# Sheet3.net
KiCad netlist of a schematic drawn in Altium Designer
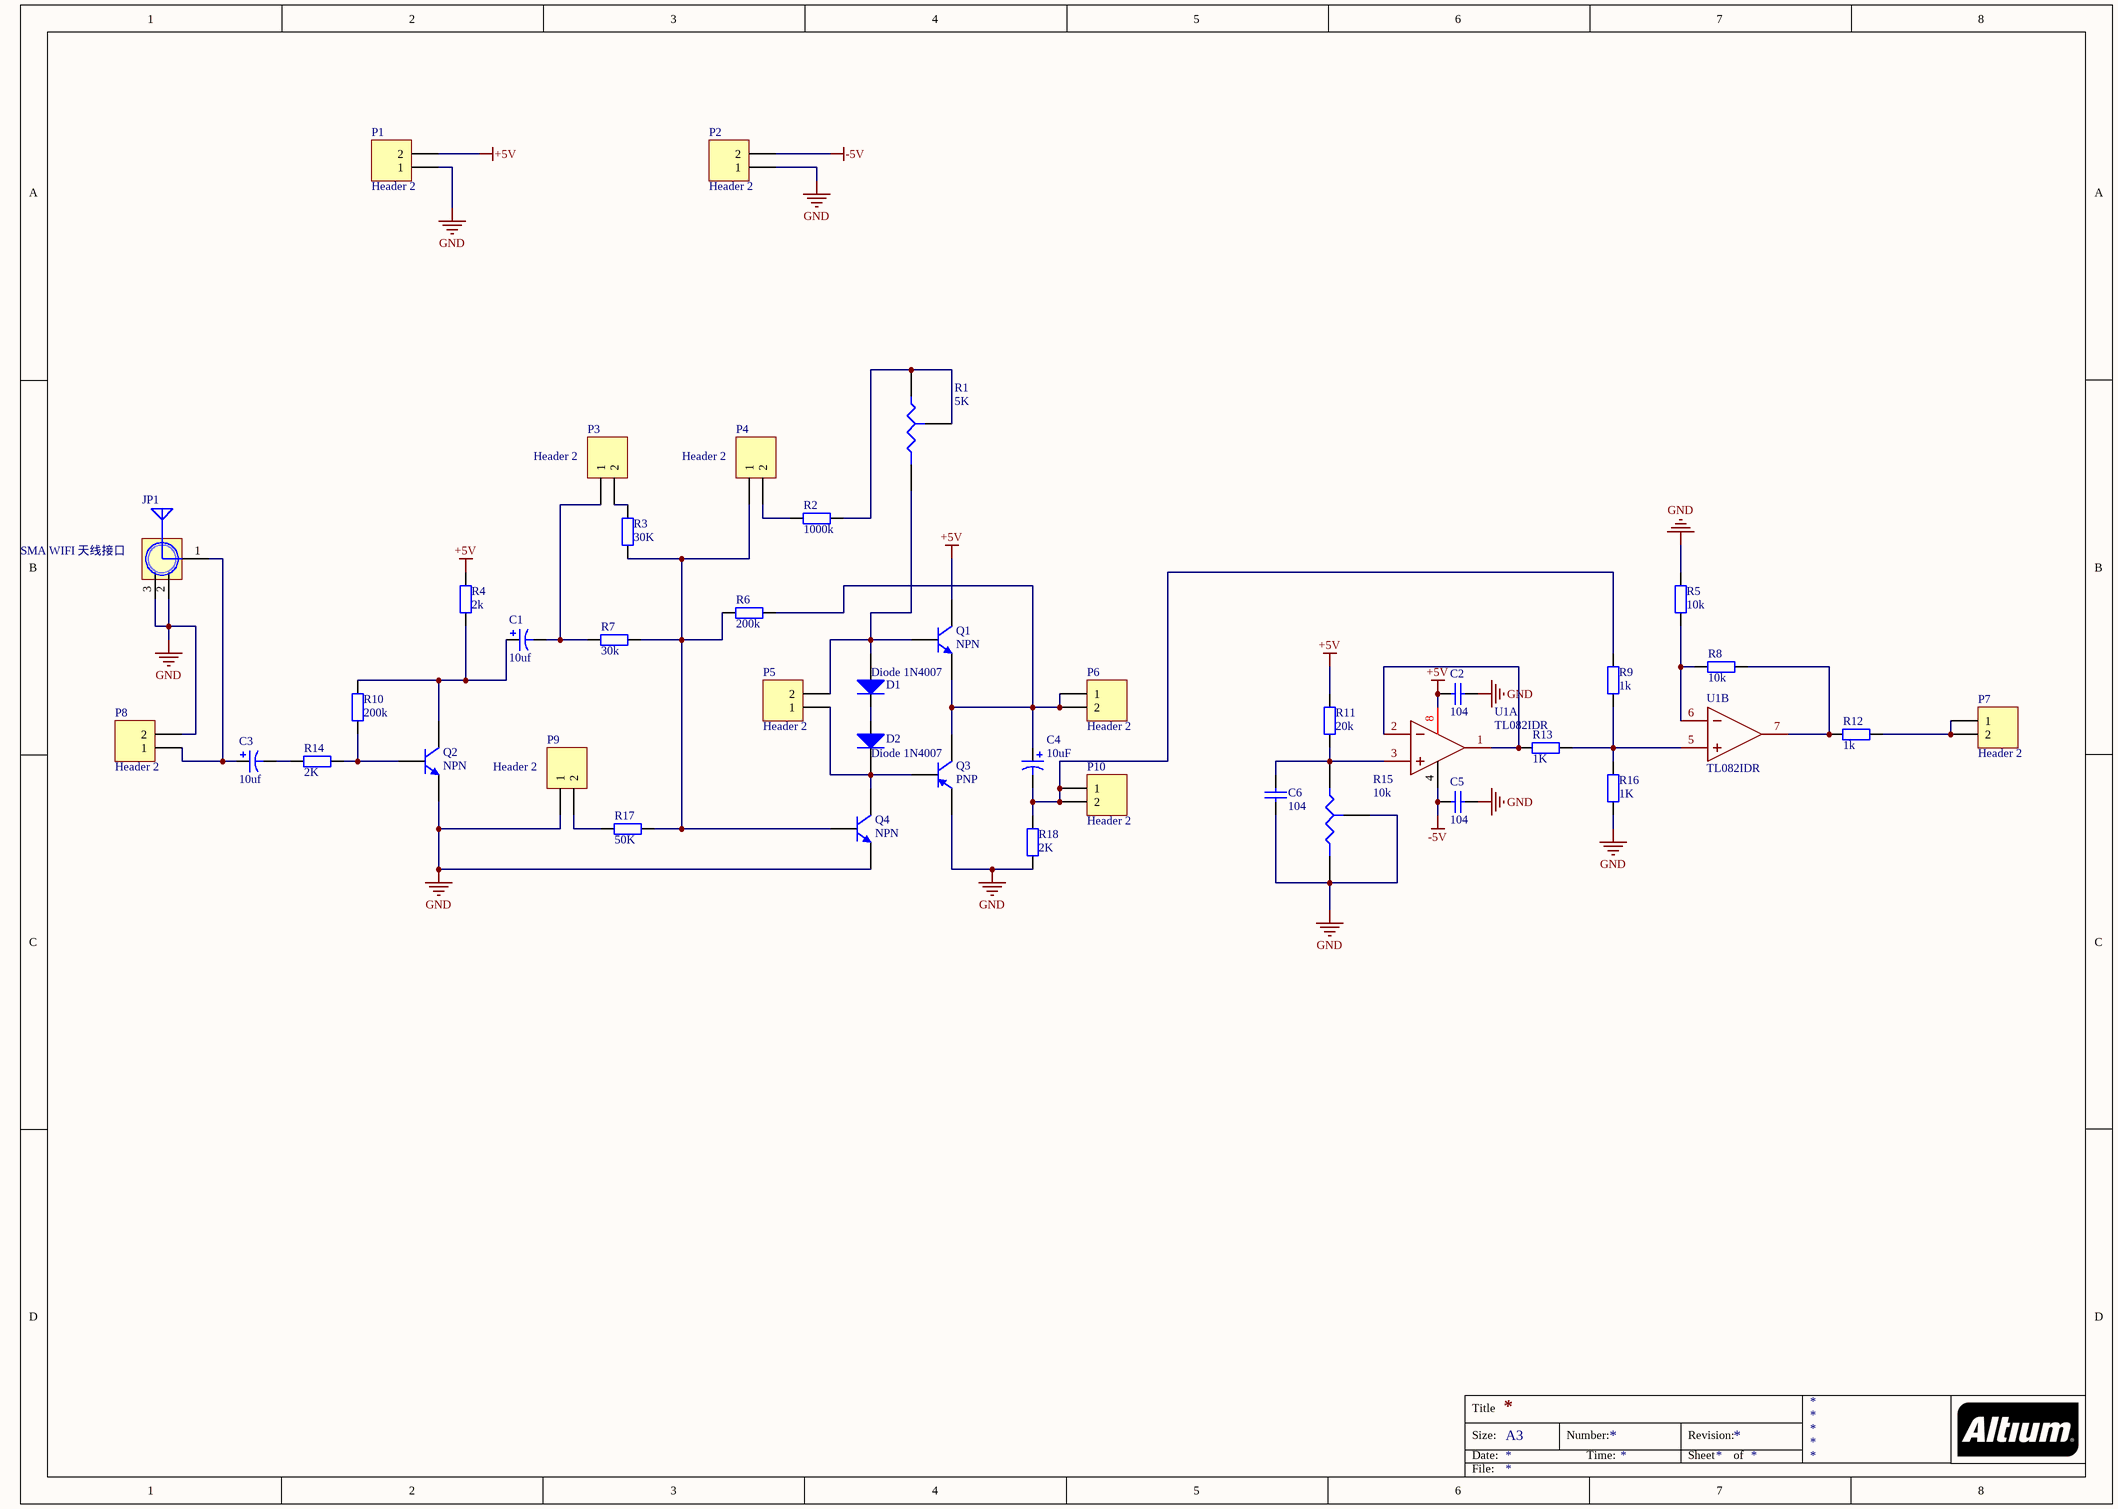
[diagram p0: Sheet3.SchDoc]

(export (version "E")
  (design (tool "Eeschema 10.0.6"))
  (components
    (comp (ref "C1")
      (value "10uf")
      (footprint "CAP 5.0*10*16 - BK")
      (description "Polarized Capacitor (Radial)")
      (fields (field (name "PUBLISHER") "Altium Limited"))
      (libsource (lib "Miscellaneous Devices") (part "Cap Pol1"))
    )
    (comp (ref "C2")
      (value "104")
      (footprint "CC 2.2*5")
      (description "Capacitor")
      (fields (field (name "PUBLISHER") "Altium Limited"))
      (libsource (lib "Miscellaneous Devices") (part "Cap"))
    )
    (comp (ref "C3")
      (value "10uf")
      (footprint "CAP 5.0*10*16 - BK")
      (description "Polarized Capacitor (Radial)")
      (fields (field (name "PUBLISHER") "Altium Limited"))
      (libsource (lib "Miscellaneous Devices") (part "Cap Pol1"))
    )
    (comp (ref "C4")
      (value "10uF")
      (footprint "CAP 5.0*10*16 - BK")
      (description "Polarized Capacitor (Radial)")
      (fields (field (name "PUBLISHER") "Altium Limited"))
      (libsource (lib "Miscellaneous Devices") (part "Cap Pol1"))
    )
    (comp (ref "C5")
      (value "104")
      (footprint "CC 2.2*5")
      (description "Capacitor")
      (fields (field (name "PUBLISHER") "Altium Limited"))
      (libsource (lib "Miscellaneous Devices") (part "Cap"))
    )
    (comp (ref "C6")
      (value "104")
      (footprint "CC 2.2*5")
      (description "Capacitor")
      (fields (field (name "PUBLISHER") "Altium Limited"))
      (libsource (lib "Miscellaneous Devices") (part "Cap"))
    )
    (comp (ref "D1")
      (value "Diode 1N4007")
      (footprint "DO-41")
      (description "1 Amp General Purpose Rectifier")
      (fields (field (name "PUBLISHER") "Altium Limited"))
      (libsource (lib "Miscellaneous Devices") (part "Diode 1N4007"))
    )
    (comp (ref "D2")
      (value "Diode 1N4007")
      (footprint "DO-41")
      (description "1 Amp General Purpose Rectifier")
      (fields (field (name "PUBLISHER") "Altium Limited"))
      (libsource (lib "Miscellaneous Devices") (part "Diode 1N4007"))
    )
    (comp (ref "JP1")
      (value "SMA WIFI 天线接口")
      (footprint "SMA-KE-LI")
      (description "SMA-2.4G射频天线接口")
      (fields (field (name "版权归属") "源创客"))
      (libsource (lib "14.1 - 天线") (part "SMA"))
    )
    (comp (ref "P1")
      (value "Header 2")
      (footprint "XH2.54-LI-2P")
      (description "Header, 2-Pin")
      (fields (field (name "PUBLISHER") "Altium Limited"))
      (libsource (lib "") (part "Header 2_1"))
    )
    (comp (ref "P2")
      (value "Header 2")
      (footprint "XH2.54-LI-2P")
      (description "Header, 2-Pin")
      (fields (field (name "PUBLISHER") "Altium Limited"))
      (libsource (lib "") (part "Header 2_1"))
    )
    (comp (ref "P3")
      (value "Header 2")
      (footprint "XH2.54-LI-2P")
      (description "Header, 2-Pin")
      (fields (field (name "PUBLISHER") "Altium Limited"))
      (libsource (lib "Miscellaneous Connectors") (part "Header 2"))
    )
    (comp (ref "P4")
      (value "Header 2")
      (footprint "XH2.54-LI-2P")
      (description "Header, 2-Pin")
      (fields (field (name "PUBLISHER") "Altium Limited"))
      (libsource (lib "Miscellaneous Connectors") (part "Header 2"))
    )
    (comp (ref "P5")
      (value "Header 2")
      (footprint "XH2.54-LI-2P")
      (description "Header, 2-Pin")
      (fields (field (name "PUBLISHER") "Altium Limited"))
      (libsource (lib "") (part "Header 2_1"))
    )
    (comp (ref "P6")
      (value "Header 2")
      (footprint "HDR2.54-LI-2P")
      (description "Header, 2-Pin")
      (fields (field (name "PUBLISHER") "Altium Limited"))
      (libsource (lib "") (part "Header 2_2"))
    )
    (comp (ref "P7")
      (value "Header 2")
      (footprint "XH2.54-LI-2P")
      (description "Header, 2-Pin")
      (fields (field (name "PUBLISHER") "Altium Limited"))
      (libsource (lib "") (part "Header 2_2"))
    )
    (comp (ref "P8")
      (value "Header 2")
      (footprint "XH2.54-LI-2P")
      (description "Header, 2-Pin")
      (fields (field (name "PUBLISHER") "Altium Limited"))
      (libsource (lib "") (part "Header 2_1"))
    )
    (comp (ref "P9")
      (value "Header 2")
      (footprint "XH2.54-LI-2P")
      (description "Header, 2-Pin")
      (fields (field (name "PUBLISHER") "Altium Limited"))
      (libsource (lib "Miscellaneous Connectors") (part "Header 2"))
    )
    (comp (ref "P10")
      (value "Header 2")
      (footprint "XH2.54-LI-2P")
      (description "Header, 2-Pin")
      (fields (field (name "PUBLISHER") "Altium Limited"))
      (libsource (lib "") (part "Header 2_2"))
    )
    (comp (ref "Q1")
      (value "NPN")
      (footprint "TO92")
      (description "NPN Bipolar Transistor")
      (fields (field (name "PUBLISHER") "Altium Limited"))
      (libsource (lib "Miscellaneous Devices") (part "NPN"))
    )
    (comp (ref "Q2")
      (value "NPN")
      (footprint "TO92")
      (description "NPN Bipolar Transistor")
      (fields (field (name "PUBLISHER") "Altium Limited"))
      (libsource (lib "Miscellaneous Devices") (part "NPN"))
    )
    (comp (ref "Q3")
      (value "PNP")
      (footprint "TO92")
      (description "PNP Bipolar Transistor")
      (fields (field (name "PUBLISHER") "Altium Limited"))
      (libsource (lib "Miscellaneous Devices") (part "PNP"))
    )
    (comp (ref "Q4")
      (value "NPN")
      (footprint "TO92")
      (description "NPN Bipolar Transistor")
      (fields (field (name "PUBLISHER") "Altium Limited"))
      (libsource (lib "Miscellaneous Devices") (part "NPN"))
    )
    (comp (ref "R1")
      (value "5K")
      (footprint "3296W")
      (description "Tapped Resistor")
      (fields (field (name "PUBLISHER") "Altium Limited"))
      (libsource (lib "Miscellaneous Devices") (part "Res Tap"))
    )
    (comp (ref "R2")
      (value "1000k")
      (footprint "AXIAL0.4-1/4W")
      (description "Resistor")
      (fields (field (name "PUBLISHER") "Altium Limited"))
      (libsource (lib "Miscellaneous Devices") (part "Res2"))
    )
    (comp (ref "R3")
      (value "30K")
      (footprint "AXIAL0.4-1/4W")
      (description "Resistor")
      (fields (field (name "PUBLISHER") "Altium Limited"))
      (libsource (lib "") (part "Res2_2"))
    )
    (comp (ref "R4")
      (value "2k")
      (footprint "AXIAL0.4-1/4W")
      (description "Resistor")
      (fields (field (name "PUBLISHER") "Altium Limited"))
      (libsource (lib "") (part "Res2_3"))
    )
    (comp (ref "R5")
      (value "10k")
      (footprint "AXIAL0.4-1/4W")
      (description "Resistor")
      (fields (field (name "PUBLISHER") "Altium Limited"))
      (libsource (lib "") (part "Res2_3"))
    )
    (comp (ref "R6")
      (value "200k")
      (footprint "AXIAL0.4-1/4W")
      (description "Resistor")
      (fields (field (name "PUBLISHER") "Altium Limited"))
      (libsource (lib "") (part "Res2_1"))
    )
    (comp (ref "R7")
      (value "30k")
      (footprint "AXIAL0.4-1/4W")
      (description "Resistor")
      (fields (field (name "PUBLISHER") "Altium Limited"))
      (libsource (lib "") (part "Res2_1"))
    )
    (comp (ref "R8")
      (value "10k")
      (footprint "AXIAL0.4-1/4W")
      (description "Resistor")
      (fields (field (name "PUBLISHER") "Altium Limited"))
      (libsource (lib "") (part "Res2_1"))
    )
    (comp (ref "R9")
      (value "1k")
      (footprint "AXIAL0.4-1/4W")
      (description "Resistor")
      (fields (field (name "PUBLISHER") "Altium Limited"))
      (libsource (lib "") (part "Res2_2"))
    )
    (comp (ref "R10")
      (value "200k")
      (footprint "AXIAL0.4-1/4W")
      (description "Resistor")
      (fields (field (name "PUBLISHER") "Altium Limited"))
      (libsource (lib "") (part "Res2_2"))
    )
    (comp (ref "R11")
      (value "20k")
      (footprint "AXIAL0.4-1/4W")
      (description "Resistor")
      (fields (field (name "PUBLISHER") "Altium Limited"))
      (libsource (lib "") (part "Res2_2"))
    )
    (comp (ref "R12")
      (value "1k")
      (footprint "AXIAL0.4-1/4W")
      (description "Resistor")
      (fields (field (name "PUBLISHER") "Altium Limited"))
      (libsource (lib "") (part "Res2_1"))
    )
    (comp (ref "R13")
      (value "1K")
      (footprint "AXIAL0.4-1/4W")
      (description "Resistor")
      (fields (field (name "PUBLISHER") "Altium Limited"))
      (libsource (lib "Miscellaneous Devices") (part "Res2"))
    )
    (comp (ref "R14")
      (value "2K")
      (footprint "AXIAL0.4-1/4W")
      (description "Resistor")
      (fields (field (name "PUBLISHER") "Altium Limited"))
      (libsource (lib "Miscellaneous Devices") (part "Res2"))
    )
    (comp (ref "R15")
      (value "10k")
      (footprint "3296W")
      (description "Tapped Resistor")
      (fields (field (name "PUBLISHER") "Altium Limited"))
      (libsource (lib "Miscellaneous Devices") (part "Res Tap"))
    )
    (comp (ref "R16")
      (value "1K")
      (footprint "AXIAL0.4-1/4W")
      (description "Resistor")
      (fields (field (name "PUBLISHER") "Altium Limited"))
      (libsource (lib "") (part "Res2_2"))
    )
    (comp (ref "R17")
      (value "50K")
      (footprint "AXIAL0.4-1/4W")
      (description "Resistor")
      (fields (field (name "PUBLISHER") "Altium Limited"))
      (libsource (lib "Miscellaneous Devices") (part "Res2"))
    )
    (comp (ref "R18")
      (value "2K")
      (footprint "AXIAL0.4-1/4W")
      (description "Resistor")
      (fields (field (name "PUBLISHER") "Altium Limited"))
      (libsource (lib "") (part "Res2_3"))
    )
    (comp (ref "U1")
      (value "TL082IDR")
      (footprint "DIP8-300_MH")
      (description "Num:C6966")
      (libsource (lib "User") (part "TL082IDR"))
    )
  )
  (nets
    (net (code "1") (name "+5V") (class "Default")
      (node (ref "C2") (pin "2") (pinfunction "2_2") (pintype "passive"))
      (node (ref "P1") (pin "2") (pinfunction "2_2") (pintype "passive"))
      (node (ref "Q1") (pin "1") (pinfunction "C_1") (pintype "passive"))
      (node (ref "R11") (pin "2") (pinfunction "2_2") (pintype "passive"))
      (node (ref "R4") (pin "1") (pinfunction "1_1") (pintype "passive"))
      (node (ref "U1") (pin "8") (pinfunction "VCC+_8") (pintype "passive"))
    )
    (net (code "2") (name "-5V") (class "Default")
      (node (ref "C5") (pin "2") (pinfunction "2_2") (pintype "passive"))
      (node (ref "P2") (pin "2") (pinfunction "2_2") (pintype "passive"))
      (node (ref "U1") (pin "4") (pinfunction "VCC-_4") (pintype "passive"))
    )
    (net (code "3") (name "GND") (class "Default")
      (node (ref "C2") (pin "1") (pinfunction "1_1") (pintype "passive"))
      (node (ref "C5") (pin "1") (pinfunction "1_1") (pintype "passive"))
      (node (ref "C6") (pin "1") (pinfunction "1_1") (pintype "passive"))
      (node (ref "JP1") (pin "2") (pinfunction "GND_2") (pintype "passive"))
      (node (ref "JP1") (pin "3") (pinfunction "GND_3") (pintype "passive"))
      (node (ref "P1") (pin "1") (pinfunction "1_1") (pintype "passive"))
      (node (ref "P2") (pin "1") (pinfunction "1_1") (pintype "passive"))
      (node (ref "P8") (pin "2") (pinfunction "2_2") (pintype "passive"))
      (node (ref "P9") (pin "1") (pinfunction "1_1") (pintype "passive"))
      (node (ref "Q2") (pin "3") (pinfunction "E_3") (pintype "passive"))
      (node (ref "Q3") (pin "3") (pinfunction "E_3") (pintype "passive"))
      (node (ref "Q4") (pin "3") (pinfunction "E_3") (pintype "passive"))
      (node (ref "R15") (pin "2") (pinfunction "B_2") (pintype "passive"))
      (node (ref "R15") (pin "3") (pinfunction "TAP_3") (pintype "passive"))
      (node (ref "R16") (pin "1") (pinfunction "1_1") (pintype "passive"))
      (node (ref "R18") (pin "2") (pinfunction "2_2") (pintype "passive"))
      (node (ref "R5") (pin "1") (pinfunction "1_1") (pintype "passive"))
    )
    (net (code "4") (name "Net-(C1-Pad2)") (class "Default")
      (node (ref "C1") (pin "2") (pinfunction "2_2") (pintype "passive"))
      (node (ref "P3") (pin "1") (pinfunction "1_1") (pintype "passive"))
      (node (ref "R7") (pin "2") (pinfunction "2_2") (pintype "passive"))
    )
    (net (code "5") (name "Net-(C3-Pad2)") (class "Default")
      (node (ref "C3") (pin "2") (pinfunction "2_2") (pintype "passive"))
      (node (ref "R14") (pin "1") (pinfunction "1_1") (pintype "passive"))
    )
    (net (code "6") (name "Net-(C4-Pad2)") (class "Default")
      (node (ref "C4") (pin "2") (pinfunction "2_2") (pintype "passive"))
      (node (ref "P10") (pin "1") (pinfunction "1_1") (pintype "passive"))
      (node (ref "P10") (pin "2") (pinfunction "2_2") (pintype "passive"))
      (node (ref "R18") (pin "1") (pinfunction "1_1") (pintype "passive"))
      (node (ref "R9") (pin "2") (pinfunction "2_2") (pintype "passive"))
    )
    (net (code "7") (name "Net-(D1-A)") (class "Default")
      (node (ref "D1") (pin "1") (pinfunction "A_1") (pintype "passive"))
      (node (ref "P5") (pin "2") (pinfunction "2_2") (pintype "passive"))
      (node (ref "Q1") (pin "2") (pinfunction "B_2") (pintype "passive"))
      (node (ref "R1") (pin "2") (pinfunction "B_2") (pintype "passive"))
    )
    (net (code "8") (name "Net-(D1-K)") (class "Default")
      (node (ref "D1") (pin "2") (pinfunction "K_2") (pintype "passive"))
      (node (ref "D2") (pin "1") (pinfunction "A_1") (pintype "passive"))
    )
    (net (code "9") (name "Net-(D2-K)") (class "Default")
      (node (ref "D2") (pin "2") (pinfunction "K_2") (pintype "passive"))
      (node (ref "P5") (pin "1") (pinfunction "1_1") (pintype "passive"))
      (node (ref "Q3") (pin "2") (pinfunction "B_2") (pintype "passive"))
      (node (ref "Q4") (pin "1") (pinfunction "C_1") (pintype "passive"))
    )
    (net (code "10") (name "Net-(JP1-ANT)") (class "Default")
      (node (ref "C3") (pin "1") (pinfunction "1_1") (pintype "passive"))
      (node (ref "JP1") (pin "1") (pinfunction "ANT_1") (pintype "passive"))
      (node (ref "P8") (pin "1") (pinfunction "1_1") (pintype "passive"))
    )
    (net (code "11") (name "Net-(P3-Pad2)") (class "Default")
      (node (ref "P3") (pin "2") (pinfunction "2_2") (pintype "passive"))
      (node (ref "R3") (pin "2") (pinfunction "2_2") (pintype "passive"))
    )
    (net (code "12") (name "Net-(P4-Pad2)") (class "Default")
      (node (ref "P4") (pin "2") (pinfunction "2_2") (pintype "passive"))
      (node (ref "R2") (pin "1") (pinfunction "1_1") (pintype "passive"))
    )
    (net (code "13") (name "Net-(P7-Pad1)") (class "Default")
      (node (ref "P7") (pin "1") (pinfunction "1_1") (pintype "passive"))
      (node (ref "P7") (pin "2") (pinfunction "2_2") (pintype "passive"))
      (node (ref "R12") (pin "1") (pinfunction "1_1") (pintype "passive"))
    )
    (net (code "14") (name "Net-(P9-Pad2)") (class "Default")
      (node (ref "P9") (pin "2") (pinfunction "2_2") (pintype "passive"))
      (node (ref "R17") (pin "1") (pinfunction "1_1") (pintype "passive"))
    )
    (net (code "15") (name "Net-(Q1-E)") (class "Default")
      (node (ref "C4") (pin "1") (pinfunction "1_1") (pintype "passive"))
      (node (ref "P6") (pin "1") (pinfunction "1_1") (pintype "passive"))
      (node (ref "P6") (pin "2") (pinfunction "2_2") (pintype "passive"))
      (node (ref "Q1") (pin "3") (pinfunction "E_3") (pintype "passive"))
      (node (ref "Q3") (pin "1") (pinfunction "C_1") (pintype "passive"))
      (node (ref "R6") (pin "1") (pinfunction "1_1") (pintype "passive"))
    )
    (net (code "16") (name "Net-(Q2-B)") (class "Default")
      (node (ref "Q2") (pin "2") (pinfunction "B_2") (pintype "passive"))
      (node (ref "R10") (pin "1") (pinfunction "1_1") (pintype "passive"))
      (node (ref "R14") (pin "2") (pinfunction "2_2") (pintype "passive"))
    )
    (net (code "17") (name "Net-(Q2-C)") (class "Default")
      (node (ref "C1") (pin "1") (pinfunction "1_1") (pintype "passive"))
      (node (ref "Q2") (pin "1") (pinfunction "C_1") (pintype "passive"))
      (node (ref "R10") (pin "2") (pinfunction "2_2") (pintype "passive"))
      (node (ref "R4") (pin "2") (pinfunction "2_2") (pintype "passive"))
    )
    (net (code "18") (name "Net-(Q4-B)") (class "Default")
      (node (ref "P4") (pin "1") (pinfunction "1_1") (pintype "passive"))
      (node (ref "Q4") (pin "2") (pinfunction "B_2") (pintype "passive"))
      (node (ref "R17") (pin "2") (pinfunction "2_2") (pintype "passive"))
      (node (ref "R3") (pin "1") (pinfunction "1_1") (pintype "passive"))
      (node (ref "R6") (pin "2") (pinfunction "2_2") (pintype "passive"))
      (node (ref "R7") (pin "1") (pinfunction "1_1") (pintype "passive"))
    )
    (net (code "19") (name "Net-(R1-A)") (class "Default")
      (node (ref "R1") (pin "1") (pinfunction "A_1") (pintype "passive"))
      (node (ref "R1") (pin "3") (pinfunction "TAP_3") (pintype "passive"))
      (node (ref "R2") (pin "2") (pinfunction "2_2") (pintype "passive"))
    )
    (net (code "20") (name "Net-(R15-A)") (class "Default")
      (node (ref "C6") (pin "2") (pinfunction "2_2") (pintype "passive"))
      (node (ref "R11") (pin "1") (pinfunction "1_1") (pintype "passive"))
      (node (ref "R15") (pin "1") (pinfunction "A_1") (pintype "passive"))
      (node (ref "U1") (pin "3") (pinfunction "IN1+_3") (pintype "passive"))
    )
    (net (code "21") (name "Net-(U1A-IN1-)") (class "Default")
      (node (ref "R13") (pin "1") (pinfunction "1_1") (pintype "passive"))
      (node (ref "U1") (pin "1") (pinfunction "OUT1_1") (pintype "passive"))
      (node (ref "U1") (pin "2") (pinfunction "IN1-_2") (pintype "passive"))
    )
    (net (code "22") (name "Net-(U1B-IN2+)") (class "Default")
      (node (ref "R13") (pin "2") (pinfunction "2_2") (pintype "passive"))
      (node (ref "R16") (pin "2") (pinfunction "2_2") (pintype "passive"))
      (node (ref "R9") (pin "1") (pinfunction "1_1") (pintype "passive"))
      (node (ref "U1") (pin "5") (pinfunction "IN2+_5") (pintype "passive"))
    )
    (net (code "23") (name "Net-(U1B-IN2-)") (class "Default")
      (node (ref "R5") (pin "2") (pinfunction "2_2") (pintype "passive"))
      (node (ref "R8") (pin "2") (pinfunction "2_2") (pintype "passive"))
      (node (ref "U1") (pin "6") (pinfunction "IN2-_6") (pintype "passive"))
    )
    (net (code "24") (name "Net-(U1B-OUT2)") (class "Default")
      (node (ref "R12") (pin "2") (pinfunction "2_2") (pintype "passive"))
      (node (ref "R8") (pin "1") (pinfunction "1_1") (pintype "passive"))
      (node (ref "U1") (pin "7") (pinfunction "OUT2_7") (pintype "passive"))
    )
  )
)
